# NB-Blue.net
KiCad netlist of a schematic drawn in Altium Designer
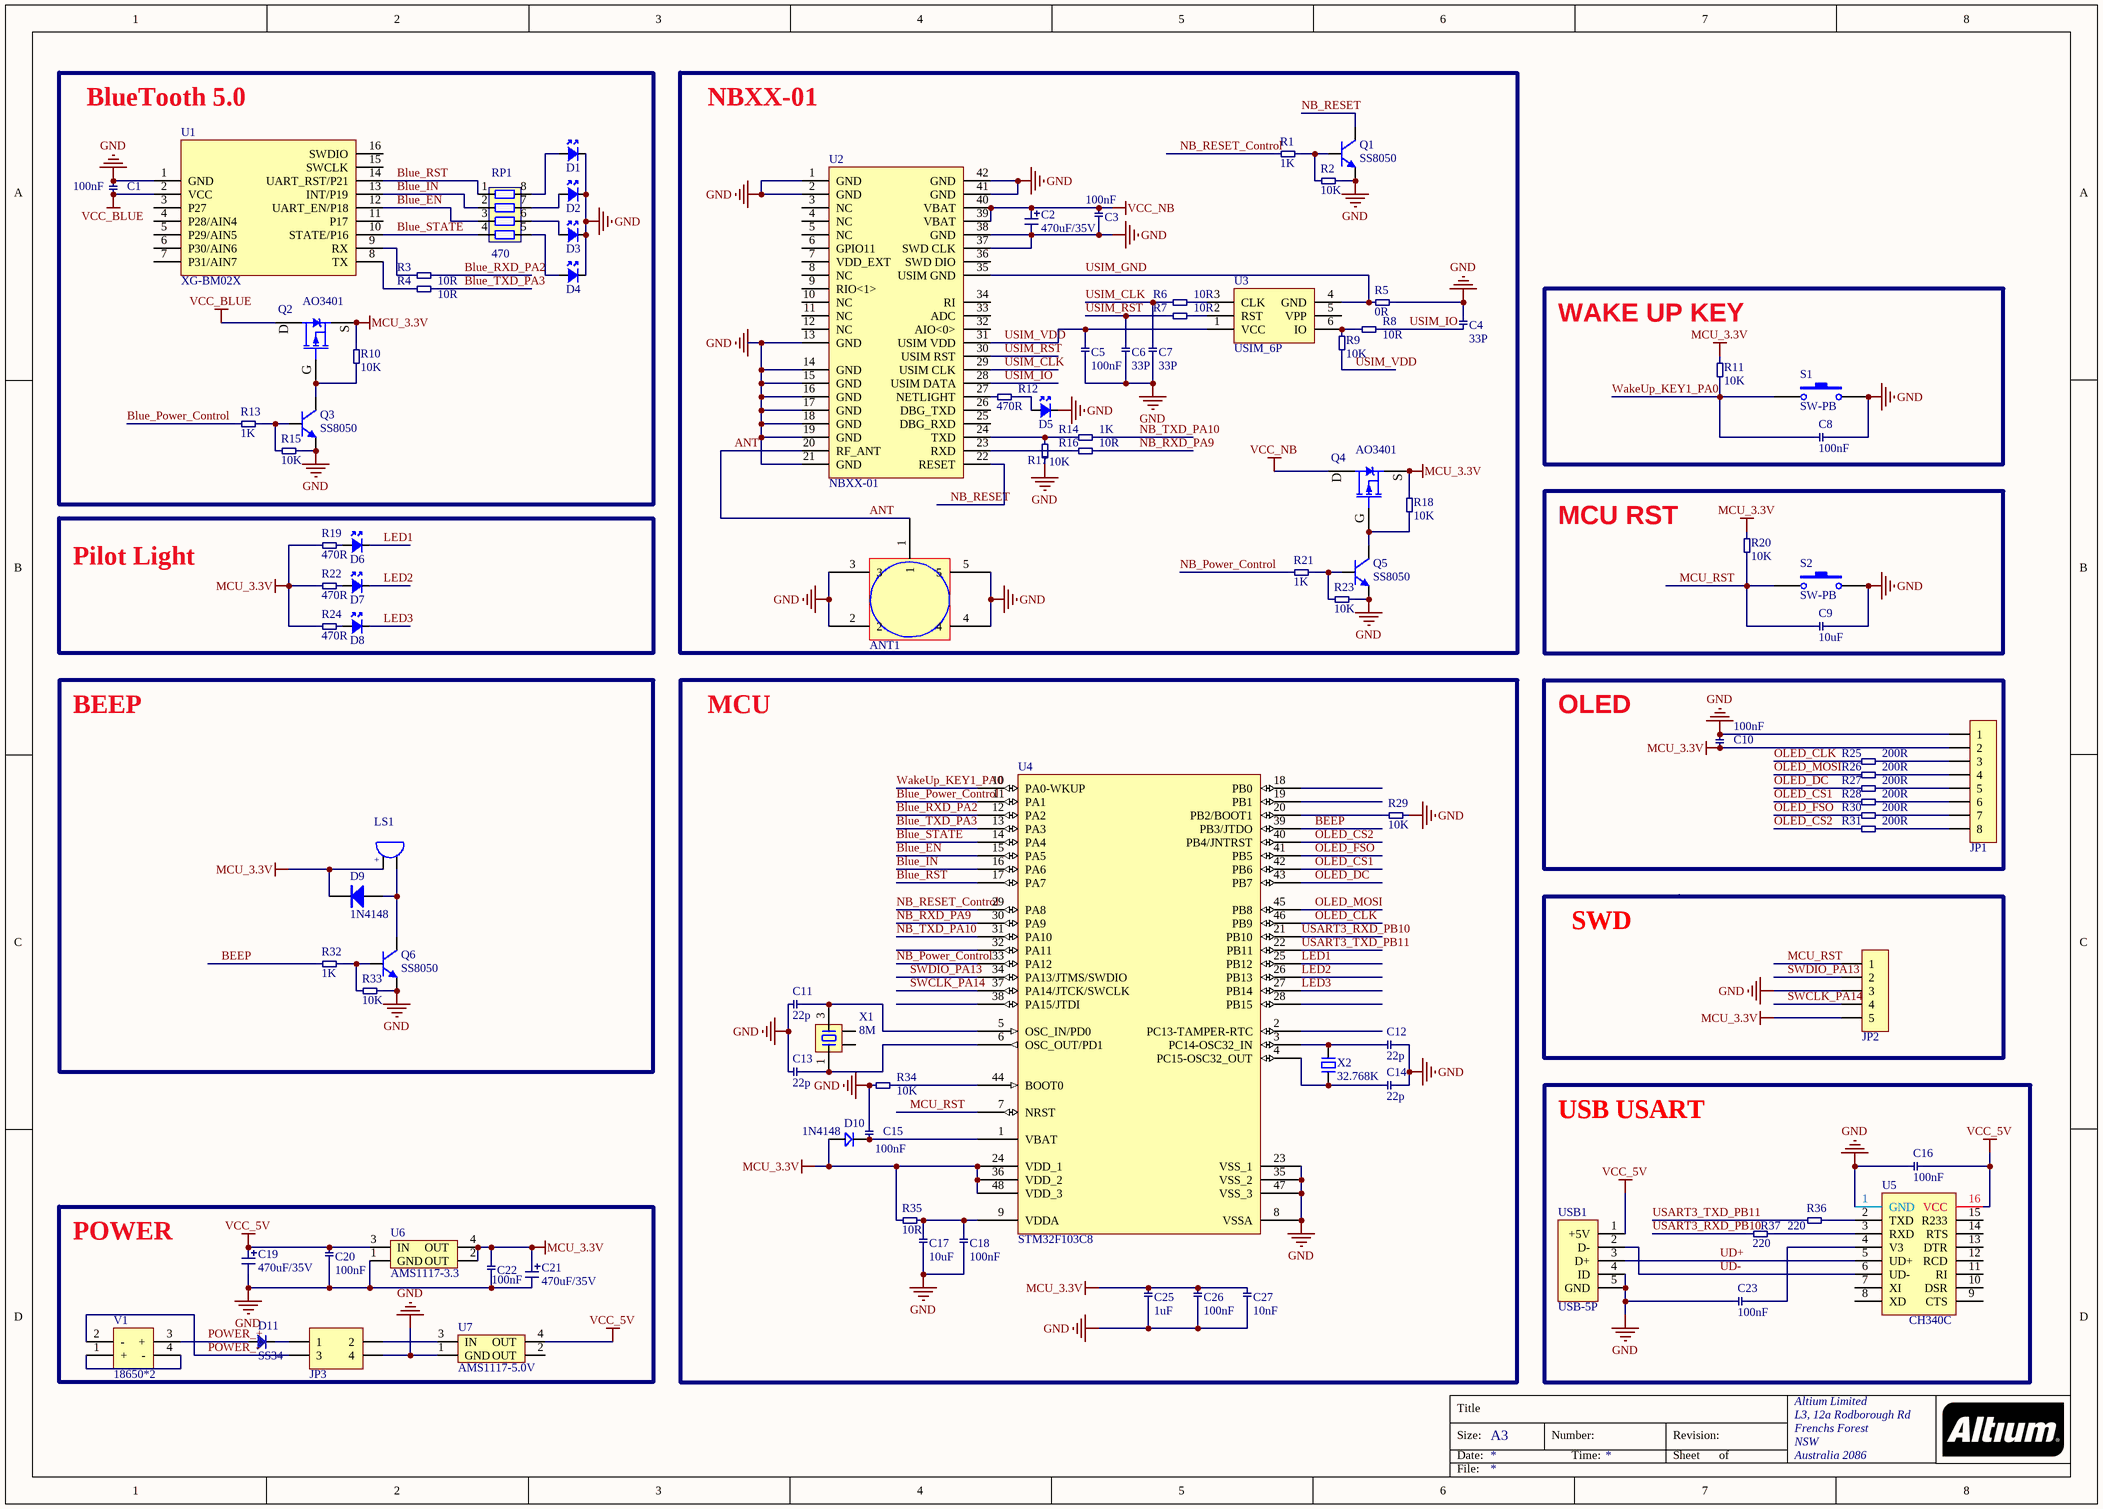
[diagram p0: NB-Blue.SchDoc]

(export (version "E")
  (design (tool "Eeschema 10.0.6"))
  (components
    (comp (ref "ANT1")
      (value "ANT")
      (footprint "SMA_FR")
      (description "SMA天线座")
      (libsource (lib "转接板顶板") (part "ANT"))
    )
    (comp (ref "C1") (value "100nF") (footprint "0603CC") (libsource (lib "LFZ@WLP") (part "cap")))
    (comp (ref "C2") (value "470uF/35V") (footprint "C3216") (libsource (lib "LFZ@WLP") (part "Ecap")))
    (comp (ref "C3") (value "100nF") (footprint "0603CC") (libsource (lib "LFZ@WLP") (part "cap")))
    (comp (ref "C4") (value "33P") (footprint "0603CC") (libsource (lib "LFZ@WLP") (part "cap")))
    (comp (ref "C5") (value "100nF") (footprint "0603CC") (libsource (lib "LFZ@WLP") (part "cap")))
    (comp (ref "C6") (value "33P") (footprint "0603CC") (libsource (lib "LFZ@WLP") (part "cap")))
    (comp (ref "C7") (value "33P") (footprint "0603CC") (libsource (lib "LFZ@WLP") (part "cap")))
    (comp (ref "C8") (value "100nF") (footprint "0603CC") (libsource (lib "LFZ@WLP") (part "cap")))
    (comp (ref "C9") (value "10uF") (footprint "0603CC") (libsource (lib "LFZ@WLP") (part "cap")))
    (comp (ref "C10") (value "100nF") (footprint "0603CC") (libsource (lib "LFZ@WLP") (part "cap")))
    (comp (ref "C11") (value "22p") (footprint "0603CC") (libsource (lib "LFZ@WLP") (part "cap")))
    (comp (ref "C12") (value "22p") (footprint "0603CC") (libsource (lib "LFZ@WLP") (part "cap")))
    (comp (ref "C13") (value "22p") (footprint "0603CC") (libsource (lib "LFZ@WLP") (part "cap")))
    (comp (ref "C14") (value "22p") (footprint "0603CC") (libsource (lib "LFZ@WLP") (part "cap")))
    (comp (ref "C15") (value "100nF") (footprint "0603CC") (libsource (lib "LFZ@WLP") (part "cap")))
    (comp (ref "C16") (value "100nF") (footprint "0603CC") (libsource (lib "LFZ@WLP") (part "cap")))
    (comp (ref "C17") (value "10uF") (footprint "0603CC") (libsource (lib "LFZ@WLP") (part "cap")))
    (comp (ref "C18") (value "100nF") (footprint "0603CC") (libsource (lib "LFZ@WLP") (part "cap")))
    (comp (ref "C19") (value "470uF/35V") (footprint "CD A(3216)") (libsource (lib "LFZ@WLP") (part "Ecap")))
    (comp (ref "C20") (value "100nF") (footprint "0603CC") (libsource (lib "LFZ@WLP") (part "cap")))
    (comp (ref "C21") (value "470uF/35V") (footprint "C3216") (libsource (lib "LFZ@WLP") (part "Ecap")))
    (comp (ref "C22") (value "100nF") (footprint "0603CC") (libsource (lib "LFZ@WLP") (part "cap")))
    (comp (ref "C23") (value "100nF") (footprint "0603CC") (libsource (lib "LFZ@WLP") (part "cap")))
    (comp (ref "C25") (value "1uF") (footprint "0603CC") (libsource (lib "LFZ@WLP") (part "cap")))
    (comp (ref "C26") (value "100nF") (footprint "0603CC") (libsource (lib "LFZ@WLP") (part "cap")))
    (comp (ref "C27") (value "10nF") (footprint "0603CC") (libsource (lib "LFZ@WLP") (part "cap")))
    (comp (ref "D1") (value "LED") (footprint "LED 0603G") (libsource (lib "LFZ@WLP") (part "LED")))
    (comp (ref "D2") (value "LED") (footprint "LED 0603G") (libsource (lib "LFZ@WLP") (part "LED")))
    (comp (ref "D3") (value "LED") (footprint "LED 0603G") (libsource (lib "LFZ@WLP") (part "LED")))
    (comp (ref "D4") (value "LED") (footprint "LED 0603G") (libsource (lib "LFZ@WLP") (part "LED")))
    (comp (ref "D5") (value "LED") (footprint "LED 0603G") (libsource (lib "LFZ@WLP") (part "LED")))
    (comp (ref "D6") (value "LED") (footprint "LED 3MM-G") (libsource (lib "LFZ@WLP") (part "LED")))
    (comp (ref "D7") (value "LED") (footprint "LED 3MM-G") (libsource (lib "LFZ@WLP") (part "LED")))
    (comp (ref "D8") (value "LED") (footprint "LED 3MM-G") (libsource (lib "LFZ@WLP") (part "LED")))
    (comp (ref "D9")
      (value "1N4148")
      (footprint "MINI_MELF (LL34)")
      (description "高速开关二极管")
      (fields (field (name "版权归属") "源创客"))
      (libsource (lib "8.1   - 二极管-整流桥") (part "1N4148"))
    )
    (comp (ref "D10")
      (value "1N4148")
      (footprint "MINI_MELF (LL34)")
      (libsource (lib "WarShip V3 STM32103封装库") (part "D"))
    )
    (comp (ref "D11") (value "SS34") (footprint "SMA") (libsource (lib "Diod") (part "Diod")))
    (comp (ref "JP1")
      (value "HDR-1X8")
      (footprint "HDR2.54-M-LI-8P")
      (description "8P接插件")
      (fields (field (name "版权归属") "源创客"))
      (libsource (lib "4.5   - 接插件-脚距2.54") (part "Header 8"))
    )
    (comp (ref "JP2")
      (value "HDR-1X5")
      (footprint "HDR2.54-LI-5P")
      (description "5P接插件")
      (fields (field (name "版权归属") "源创客"))
      (libsource (lib "4.5   - 接插件-脚距2.54") (part "Header 5"))
    )
    (comp (ref "JP3")
      (value "Header2X2")
      (footprint "HDR2.54-LI-2x2P")
      (description "2*2P接插件")
      (fields (field (name "版权归属") "源创客"))
      (libsource (lib "4.5   - 接插件-脚距2.54") (part "Header 2X2"))
    )
    (comp (ref "LS1")
      (value "DC5V")
      (footprint "BEEP 5x9x5.5")
      (description "蜂鸣器")
      (fields (field (name "版权归属") "源创客"))
      (libsource (lib "15.1 - 未分类器件") (part "BEEP"))
    )
    (comp (ref "Q1")
      (value "SS8050")
      (footprint "SOT23-3N")
      (description "高频放大-NPN型")
      (fields (field (name "版权归属") "源创客"))
      (libsource (lib "6.2   - 三极管") (part "8050-SMD"))
    )
    (comp (ref "Q2")
      (value "AO3401")
      (footprint "SOT23-3N")
      (description "P沟道场效应管")
      (fields (field (name "版权归属") "源创客"))
      (libsource (lib "6.1   - 场效应管-可控硅") (part "SI2301"))
    )
    (comp (ref "Q3")
      (value "SS8050")
      (footprint "SOT23-3N")
      (description "高频放大-NPN型")
      (fields (field (name "版权归属") "源创客"))
      (libsource (lib "6.2   - 三极管") (part "8050-SMD"))
    )
    (comp (ref "Q4")
      (value "AO3401")
      (footprint "SOT23-3N")
      (description "P沟道场效应管")
      (fields (field (name "版权归属") "源创客"))
      (libsource (lib "6.1   - 场效应管-可控硅") (part "SI2301"))
    )
    (comp (ref "Q5")
      (value "SS8050")
      (footprint "SOT23-3N")
      (description "高频放大-NPN型")
      (fields (field (name "版权归属") "源创客"))
      (libsource (lib "6.2   - 三极管") (part "8050-SMD"))
    )
    (comp (ref "Q6")
      (value "SS8050")
      (footprint "SOT23-3N")
      (description "高频放大-NPN型")
      (fields (field (name "版权归属") "源创客"))
      (libsource (lib "6.2   - 三极管") (part "8050-SMD"))
    )
    (comp (ref "R1") (value "1K") (footprint "0603RR") (libsource (lib "LFZ@WLP") (part "res")))
    (comp (ref "R2") (value "10K") (footprint "0603RR") (libsource (lib "LFZ@WLP") (part "res")))
    (comp (ref "R3") (value "10R") (footprint "0603RR") (libsource (lib "LFZ@WLP") (part "res")))
    (comp (ref "R4") (value "10R") (footprint "0603RR") (libsource (lib "LFZ@WLP") (part "res")))
    (comp (ref "R5") (value "0R") (footprint "0603RR") (libsource (lib "LFZ@WLP") (part "res")))
    (comp (ref "R6") (value "10R") (footprint "0603RR") (libsource (lib "LFZ@WLP") (part "res")))
    (comp (ref "R7") (value "10R") (footprint "0603RR") (libsource (lib "LFZ@WLP") (part "res")))
    (comp (ref "R8") (value "10R") (footprint "0603RR") (libsource (lib "LFZ@WLP") (part "res")))
    (comp (ref "R9") (value "10K") (footprint "0603RR") (libsource (lib "LFZ@WLP") (part "res")))
    (comp (ref "R10") (value "10K") (footprint "0603RR") (libsource (lib "LFZ@WLP") (part "res")))
    (comp (ref "R11") (value "10K") (footprint "0603RR") (libsource (lib "LFZ@WLP") (part "res")))
    (comp (ref "R12") (value "470R") (footprint "0603RR") (libsource (lib "LFZ@WLP") (part "res")))
    (comp (ref "R13") (value "1K") (footprint "0603RR") (libsource (lib "LFZ@WLP") (part "res")))
    (comp (ref "R14") (value "1K") (footprint "0603RR") (libsource (lib "LFZ@WLP") (part "res")))
    (comp (ref "R15") (value "10K") (footprint "0603RR") (libsource (lib "LFZ@WLP") (part "res")))
    (comp (ref "R16") (value "10R") (footprint "0603RR") (libsource (lib "LFZ@WLP") (part "res")))
    (comp (ref "R17") (value "10K") (footprint "0603RR") (libsource (lib "LFZ@WLP") (part "res")))
    (comp (ref "R18") (value "10K") (footprint "0603RR") (libsource (lib "LFZ@WLP") (part "res")))
    (comp (ref "R19") (value "470R") (footprint "0603RR") (libsource (lib "LFZ@WLP") (part "res")))
    (comp (ref "R20") (value "10K") (footprint "0603RR") (libsource (lib "LFZ@WLP") (part "res")))
    (comp (ref "R21") (value "1K") (footprint "0603RR") (libsource (lib "LFZ@WLP") (part "res")))
    (comp (ref "R22") (value "470R") (footprint "0603RR") (libsource (lib "LFZ@WLP") (part "res")))
    (comp (ref "R23") (value "10K") (footprint "0603RR") (libsource (lib "LFZ@WLP") (part "res")))
    (comp (ref "R24") (value "470R") (footprint "0603RR") (libsource (lib "LFZ@WLP") (part "res")))
    (comp (ref "R25") (value "200R") (footprint "0603RR") (libsource (lib "LFZ@WLP") (part "res")))
    (comp (ref "R26") (value "200R") (footprint "0603RR") (libsource (lib "LFZ@WLP") (part "res")))
    (comp (ref "R27") (value "200R") (footprint "0603RR") (libsource (lib "LFZ@WLP") (part "res")))
    (comp (ref "R28") (value "200R") (footprint "0603RR") (libsource (lib "LFZ@WLP") (part "res")))
    (comp (ref "R29") (value "10K") (footprint "0603RR") (libsource (lib "LFZ@WLP") (part "res")))
    (comp (ref "R30") (value "200R") (footprint "0603RR") (libsource (lib "LFZ@WLP") (part "res")))
    (comp (ref "R31") (value "200R") (footprint "0603RR") (libsource (lib "LFZ@WLP") (part "res")))
    (comp (ref "R32") (value "1K") (footprint "0603RR") (libsource (lib "LFZ@WLP") (part "res")))
    (comp (ref "R33") (value "10K") (footprint "0603RR") (libsource (lib "LFZ@WLP") (part "res")))
    (comp (ref "R34") (value "10K") (footprint "0603RR") (libsource (lib "LFZ@WLP") (part "res")))
    (comp (ref "R35") (value "10R") (footprint "0603RR") (libsource (lib "LFZ@WLP") (part "res")))
    (comp (ref "R36") (value "220") (footprint "0603RR") (libsource (lib "LFZ@WLP") (part "res")))
    (comp (ref "R37") (value "220") (footprint "0603RR") (libsource (lib "LFZ@WLP") (part "res")))
    (comp (ref "RP1") (value "470") (footprint "4x0603") (libsource (lib "LFZ@WLP") (part "Resistor_Pack")))
    (comp (ref "S1")
      (value "SW-PB")
      (footprint "TSW SMD-6*6*6")
      (description "Switch")
      (fields (field (name "PUBLISHER") "Altium Limited"))
      (libsource (lib "开关及电源") (part "SW-PB"))
    )
    (comp (ref "S2")
      (value "SW-PB")
      (footprint "TSW SMD-4*4*1.5")
      (description "Switch")
      (fields (field (name "PUBLISHER") "Altium Limited"))
      (libsource (lib "开关及电源") (part "SW-PB"))
    )
    (comp (ref "U1") (value "XG-BM02X") (footprint "XG-BM02X") (libsource (lib "XG-BM02") (part "XG-BM02X")))
    (comp (ref "U2")
      (value "NBXX-01")
      (footprint "X_LSD4NBN-LB05000001")
      (libsource (lib "XG-BM02") (part "NB"))
    )
    (comp (ref "U3") (value "USIM_6P") (footprint "SIM 6P 自弹") (libsource (lib "XG-BM02") (part "USIM-6P")))
    (comp (ref "U4")
      (value "STM32F103C8")
      (footprint "LQFP48 7X7_M")
      (description "Flaah:64/RAM:20/IO:36")
      (fields (field (name "版权归属") "源创客"))
      (libsource (lib "2.1   - STM32系列单片机") (part "STM32F103C8"))
    )
    (comp (ref "U5") (value "CH340C") (footprint "SOP16_L") (libsource (lib "LFZ@WLP") (part "CH340C")))
    (comp (ref "U6")
      (value "AMS1117-3.3")
      (footprint "SOT223_N")
      (libsource (lib "WarShip V3 STM32103封装库") (part "AMS1117"))
    )
    (comp (ref "U7")
      (value "AMS1117-5.0V")
      (footprint "SOT223_N")
      (libsource (lib "WarShip V3 STM32103封装库") (part "AMS1117"))
    )
    (comp (ref "USB1")
      (value "USB-5P")
      (footprint "USB-MICRO_A")
      (description "微型USB母座")
      (fields (field (name "版权归属") "源创客"))
      (libsource (lib "4.1   - 接口类") (part "USB-5P"))
    )
    (comp (ref "V1") (value "18650*2") (footprint "18650*2") (libsource (lib "XG-BM02") (part "18650-2P")))
    (comp (ref "X1")
      (value "8M")
      (footprint "OSC 3225-4P")
      (description "4脚无源晶振")
      (fields (field (name "版权归属") "源创客"))
      (libsource (lib "10.1 - 保险丝-晶振") (part "XTAL-4P"))
    )
    (comp (ref "X2")
      (value "32.768K")
      (footprint "OSC 3215-2P")
      (description "2脚无源脚晶振")
      (fields (field (name "版权归属") "源创客"))
      (libsource (lib "10.1 - 保险丝-晶振") (part "XTAL-2P"))
    )
  )
  (nets
    (net (code "1") (name "/ANT") (class "Default")
      (node (ref "ANT1") (pin "1") (pinfunction "1_1") (pintype "passive"))
      (node (ref "U2") (pin "20") (pinfunction "RF_ANT_20") (pintype "passive"))
    )
    (net (code "2") (name "/BEEP") (class "Default")
      (node (ref "R32") (pin "1") (pinfunction "1_1") (pintype "passive"))
      (node (ref "U4") (pin "39") (pinfunction "PB3/JTDO_39") (pintype "bidirectional"))
    )
    (net (code "3") (name "/Blue_EN") (class "Default")
      (node (ref "RP1") (pin "3") (pinfunction "3_3") (pintype "passive"))
      (node (ref "U1") (pin "12") (pinfunction "UART_EN/P18_12") (pintype "passive"))
      (node (ref "U4") (pin "15") (pinfunction "PA5_15") (pintype "bidirectional"))
    )
    (net (code "4") (name "/Blue_IN") (class "Default")
      (node (ref "RP1") (pin "2") (pinfunction "2_2") (pintype "passive"))
      (node (ref "U1") (pin "13") (pinfunction "INT/P19_13") (pintype "passive"))
      (node (ref "U4") (pin "16") (pinfunction "PA6_16") (pintype "bidirectional"))
    )
    (net (code "5") (name "/Blue_Power_Control") (class "Default")
      (node (ref "R13") (pin "1") (pinfunction "1_1") (pintype "passive"))
      (node (ref "U4") (pin "11") (pinfunction "PA1_11") (pintype "bidirectional"))
    )
    (net (code "6") (name "/Blue_RST") (class "Default")
      (node (ref "RP1") (pin "1") (pinfunction "1_1") (pintype "passive"))
      (node (ref "U1") (pin "14") (pinfunction "UART_RST/P21_14") (pintype "passive"))
      (node (ref "U4") (pin "17") (pinfunction "PA7_17") (pintype "bidirectional"))
    )
    (net (code "7") (name "/Blue_RXD_PA2") (class "Default")
      (node (ref "R3") (pin "2") (pinfunction "2_2") (pintype "passive"))
      (node (ref "U4") (pin "12") (pinfunction "PA2_12") (pintype "bidirectional"))
    )
    (net (code "8") (name "/Blue_STATE") (class "Default")
      (node (ref "RP1") (pin "4") (pinfunction "4_4") (pintype "passive"))
      (node (ref "U1") (pin "10") (pinfunction "STATE/P16_10") (pintype "passive"))
      (node (ref "U4") (pin "14") (pinfunction "PA4_14") (pintype "bidirectional"))
    )
    (net (code "9") (name "/Blue_TXD_PA3") (class "Default")
      (node (ref "R4") (pin "2") (pinfunction "2_2") (pintype "passive"))
      (node (ref "U4") (pin "13") (pinfunction "PA3_13") (pintype "bidirectional"))
    )
    (net (code "10") (name "/LED1") (class "Default")
      (node (ref "D6") (pin "2") (pinfunction "CATHODE_2") (pintype "passive"))
      (node (ref "U4") (pin "25") (pinfunction "PB12_25") (pintype "bidirectional"))
    )
    (net (code "11") (name "/LED2") (class "Default")
      (node (ref "D7") (pin "2") (pinfunction "CATHODE_2") (pintype "passive"))
      (node (ref "U4") (pin "26") (pinfunction "PB13_26") (pintype "bidirectional"))
    )
    (net (code "12") (name "/LED3") (class "Default")
      (node (ref "D8") (pin "2") (pinfunction "CATHODE_2") (pintype "passive"))
      (node (ref "U4") (pin "27") (pinfunction "PB14_27") (pintype "bidirectional"))
    )
    (net (code "13") (name "/MCU_RST") (class "Default")
      (node (ref "C9") (pin "2") (pinfunction "2_2") (pintype "passive"))
      (node (ref "JP2") (pin "1") (pinfunction "1_1") (pintype "passive"))
      (node (ref "R20") (pin "1") (pinfunction "1_1") (pintype "passive"))
      (node (ref "S2") (pin "1") (pinfunction "1_1") (pintype "passive"))
      (node (ref "U4") (pin "7") (pinfunction "NRST_7") (pintype "bidirectional"))
    )
    (net (code "14") (name "/NB_Power_Control") (class "Default")
      (node (ref "R21") (pin "1") (pinfunction "1_1") (pintype "passive"))
      (node (ref "U4") (pin "33") (pinfunction "PA12_33") (pintype "bidirectional"))
    )
    (net (code "15") (name "/NB_RESET") (class "Default")
      (node (ref "Q1") (pin "3") (pinfunction "C_3") (pintype "passive"))
      (node (ref "U2") (pin "22") (pinfunction "RESET_22") (pintype "passive"))
    )
    (net (code "16") (name "/NB_RESET_Control") (class "Default")
      (node (ref "R1") (pin "1") (pinfunction "1_1") (pintype "passive"))
      (node (ref "U4") (pin "29") (pinfunction "PA8_29") (pintype "bidirectional"))
    )
    (net (code "17") (name "/NB_RXD_PA9") (class "Default")
      (node (ref "R16") (pin "2") (pinfunction "2_2") (pintype "passive"))
      (node (ref "U4") (pin "30") (pinfunction "PA9_30") (pintype "bidirectional"))
    )
    (net (code "18") (name "/NB_TXD_PA10") (class "Default")
      (node (ref "R14") (pin "2") (pinfunction "2_2") (pintype "passive"))
      (node (ref "U4") (pin "31") (pinfunction "PA10_31") (pintype "bidirectional"))
    )
    (net (code "19") (name "/OLED_CLK") (class "Default")
      (node (ref "R25") (pin "1") (pinfunction "1_1") (pintype "passive"))
      (node (ref "U4") (pin "46") (pinfunction "PB9_46") (pintype "bidirectional"))
    )
    (net (code "20") (name "/OLED_CS1") (class "Default")
      (node (ref "R28") (pin "1") (pinfunction "1_1") (pintype "passive"))
      (node (ref "U4") (pin "42") (pinfunction "PB6_42") (pintype "bidirectional"))
    )
    (net (code "21") (name "/OLED_CS2") (class "Default")
      (node (ref "R31") (pin "1") (pinfunction "1_1") (pintype "passive"))
      (node (ref "U4") (pin "40") (pinfunction "PB4/JNTRST_40") (pintype "bidirectional"))
    )
    (net (code "22") (name "/OLED_DC") (class "Default")
      (node (ref "R27") (pin "1") (pinfunction "1_1") (pintype "passive"))
      (node (ref "U4") (pin "43") (pinfunction "PB7_43") (pintype "bidirectional"))
    )
    (net (code "23") (name "/OLED_FSO") (class "Default")
      (node (ref "R30") (pin "1") (pinfunction "1_1") (pintype "passive"))
      (node (ref "U4") (pin "41") (pinfunction "PB5_41") (pintype "bidirectional"))
    )
    (net (code "24") (name "/OLED_MOSI") (class "Default")
      (node (ref "R26") (pin "1") (pinfunction "1_1") (pintype "passive"))
      (node (ref "U4") (pin "45") (pinfunction "PB8_45") (pintype "bidirectional"))
    )
    (net (code "25") (name "/POWER_+") (class "Default")
      (node (ref "D11") (pin "1") (pinfunction "ANODE_1") (pintype "passive"))
      (node (ref "V1") (pin "3") (pinfunction "+_3") (pintype "passive"))
    )
    (net (code "26") (name "/POWER_-") (class "Default")
      (node (ref "JP3") (pin "3") (pinfunction "3_3") (pintype "passive"))
      (node (ref "V1") (pin "2") (pinfunction "-_2") (pintype "passive"))
    )
    (net (code "27") (name "/SWCLK_PA14") (class "Default")
      (node (ref "JP2") (pin "4") (pinfunction "4_4") (pintype "passive"))
      (node (ref "U4") (pin "37") (pinfunction "PA14/JTCK/SWCLK_37") (pintype "bidirectional"))
    )
    (net (code "28") (name "/SWDIO_PA13") (class "Default")
      (node (ref "JP2") (pin "2") (pinfunction "2_2") (pintype "passive"))
      (node (ref "U4") (pin "34") (pinfunction "PA13/JTMS/SWDIO_34") (pintype "bidirectional"))
    )
    (net (code "29") (name "/UD+") (class "Default")
      (node (ref "U5") (pin "5") (pinfunction "UD+_5") (pintype "passive"))
      (node (ref "USB1") (pin "3") (pinfunction "D+_3") (pintype "passive"))
    )
    (net (code "30") (name "/UD-") (class "Default")
      (node (ref "U5") (pin "6") (pinfunction "UD-_6") (pintype "passive"))
      (node (ref "USB1") (pin "2") (pinfunction "D-_2") (pintype "passive"))
    )
    (net (code "31") (name "/USART3_RXD_PB10") (class "Default")
      (node (ref "R37") (pin "1") (pinfunction "1_1") (pintype "passive"))
      (node (ref "U4") (pin "21") (pinfunction "PB10_21") (pintype "bidirectional"))
    )
    (net (code "32") (name "/USART3_TXD_PB11") (class "Default")
      (node (ref "R36") (pin "1") (pinfunction "1_1") (pintype "passive"))
      (node (ref "U4") (pin "22") (pinfunction "PB11_22") (pintype "bidirectional"))
    )
    (net (code "33") (name "/USIM_CLK") (class "Default")
      (node (ref "C7") (pin "2") (pinfunction "2_2") (pintype "passive"))
      (node (ref "R6") (pin "1") (pinfunction "1_1") (pintype "passive"))
      (node (ref "U2") (pin "29") (pinfunction "USIM_CLK_29") (pintype "passive"))
    )
    (net (code "34") (name "/USIM_GND") (class "Default")
      (node (ref "R5") (pin "1") (pinfunction "1_1") (pintype "passive"))
      (node (ref "U2") (pin "35") (pinfunction "USIM_GND_35") (pintype "passive"))
      (node (ref "U3") (pin "4") (pinfunction "GND_4") (pintype "passive"))
    )
    (net (code "35") (name "/USIM_IO") (class "Default")
      (node (ref "C4") (pin "1") (pinfunction "1_1") (pintype "passive"))
      (node (ref "R8") (pin "1") (pinfunction "1_1") (pintype "passive"))
      (node (ref "U2") (pin "28") (pinfunction "USIM_DATA_28") (pintype "passive"))
    )
    (net (code "36") (name "/USIM_RST") (class "Default")
      (node (ref "C6") (pin "2") (pinfunction "2_2") (pintype "passive"))
      (node (ref "R7") (pin "1") (pinfunction "1_1") (pintype "passive"))
      (node (ref "U2") (pin "30") (pinfunction "USIM_RST_30") (pintype "passive"))
    )
    (net (code "37") (name "/USIM_VDD") (class "Default")
      (node (ref "C5") (pin "2") (pinfunction "2_2") (pintype "passive"))
      (node (ref "R9") (pin "1") (pinfunction "1_1") (pintype "passive"))
      (node (ref "U2") (pin "31") (pinfunction "USIM_VDD_31") (pintype "passive"))
      (node (ref "U3") (pin "1") (pinfunction "VCC_1") (pintype "passive"))
    )
    (net (code "38") (name "/WakeUp_KEY1_PA0") (class "Default")
      (node (ref "C8") (pin "1") (pinfunction "1_1") (pintype "passive"))
      (node (ref "R11") (pin "1") (pinfunction "1_1") (pintype "passive"))
      (node (ref "S1") (pin "1") (pinfunction "1_1") (pintype "passive"))
      (node (ref "U4") (pin "10") (pinfunction "PA0-WKUP_10") (pintype "bidirectional"))
    )
    (net (code "39") (name "GND") (class "Default")
      (node (ref "ANT1") (pin "2") (pinfunction "2_2") (pintype "passive"))
      (node (ref "ANT1") (pin "3") (pinfunction "3_3") (pintype "passive"))
      (node (ref "ANT1") (pin "4") (pinfunction "4_4") (pintype "passive"))
      (node (ref "ANT1") (pin "5") (pinfunction "5_5") (pintype "passive"))
      (node (ref "C1") (pin "2") (pinfunction "2_2") (pintype "passive"))
      (node (ref "C10") (pin "2") (pinfunction "2_2") (pintype "passive"))
      (node (ref "C11") (pin "1") (pinfunction "1_1") (pintype "passive"))
      (node (ref "C12") (pin "2") (pinfunction "2_2") (pintype "passive"))
      (node (ref "C13") (pin "1") (pinfunction "1_1") (pintype "passive"))
      (node (ref "C14") (pin "2") (pinfunction "2_2") (pintype "passive"))
      (node (ref "C15") (pin "2") (pinfunction "2_2") (pintype "passive"))
      (node (ref "C16") (pin "2") (pinfunction "2_2") (pintype "passive"))
      (node (ref "C17") (pin "1") (pinfunction "1_1") (pintype "passive"))
      (node (ref "C18") (pin "1") (pinfunction "1_1") (pintype "passive"))
      (node (ref "C19") (pin "2") (pinfunction "2_2") (pintype "passive"))
      (node (ref "C2") (pin "2") (pinfunction "2_2") (pintype "passive"))
      (node (ref "C20") (pin "1") (pinfunction "1_1") (pintype "passive"))
      (node (ref "C21") (pin "2") (pinfunction "2_2") (pintype "passive"))
      (node (ref "C22") (pin "1") (pinfunction "1_1") (pintype "passive"))
      (node (ref "C23") (pin "2") (pinfunction "2_2") (pintype "passive"))
      (node (ref "C25") (pin "1") (pinfunction "1_1") (pintype "passive"))
      (node (ref "C26") (pin "1") (pinfunction "1_1") (pintype "passive"))
      (node (ref "C27") (pin "1") (pinfunction "1_1") (pintype "passive"))
      (node (ref "C3") (pin "1") (pinfunction "1_1") (pintype "passive"))
      (node (ref "C4") (pin "2") (pinfunction "2_2") (pintype "passive"))
      (node (ref "C5") (pin "1") (pinfunction "1_1") (pintype "passive"))
      (node (ref "C6") (pin "1") (pinfunction "1_1") (pintype "passive"))
      (node (ref "C7") (pin "1") (pinfunction "1_1") (pintype "passive"))
      (node (ref "C8") (pin "2") (pinfunction "2_2") (pintype "passive"))
      (node (ref "C9") (pin "1") (pinfunction "1_1") (pintype "passive"))
      (node (ref "D1") (pin "2") (pinfunction "CATHODE_2") (pintype "passive"))
      (node (ref "D2") (pin "2") (pinfunction "CATHODE_2") (pintype "passive"))
      (node (ref "D3") (pin "2") (pinfunction "CATHODE_2") (pintype "passive"))
      (node (ref "D4") (pin "2") (pinfunction "CATHODE_2") (pintype "passive"))
      (node (ref "D5") (pin "2") (pinfunction "CATHODE_2") (pintype "passive"))
      (node (ref "JP1") (pin "1") (pinfunction "1_1") (pintype "passive"))
      (node (ref "JP2") (pin "3") (pinfunction "3_3") (pintype "passive"))
      (node (ref "JP3") (pin "4") (pinfunction "4_4") (pintype "passive"))
      (node (ref "Q1") (pin "2") (pinfunction "E_2") (pintype "passive"))
      (node (ref "Q3") (pin "2") (pinfunction "E_2") (pintype "passive"))
      (node (ref "Q5") (pin "2") (pinfunction "E_2") (pintype "passive"))
      (node (ref "Q6") (pin "2") (pinfunction "E_2") (pintype "passive"))
      (node (ref "R15") (pin "2") (pinfunction "2_2") (pintype "passive"))
      (node (ref "R17") (pin "2") (pinfunction "2_2") (pintype "passive"))
      (node (ref "R2") (pin "2") (pinfunction "2_2") (pintype "passive"))
      (node (ref "R23") (pin "2") (pinfunction "2_2") (pintype "passive"))
      (node (ref "R29") (pin "2") (pinfunction "2_2") (pintype "passive"))
      (node (ref "R33") (pin "2") (pinfunction "2_2") (pintype "passive"))
      (node (ref "R34") (pin "1") (pinfunction "1_1") (pintype "passive"))
      (node (ref "R5") (pin "2") (pinfunction "2_2") (pintype "passive"))
      (node (ref "S1") (pin "2") (pinfunction "2_2") (pintype "passive"))
      (node (ref "S2") (pin "2") (pinfunction "2_2") (pintype "passive"))
      (node (ref "U1") (pin "1") (pinfunction "GND_1") (pintype "passive"))
      (node (ref "U2") (pin "1") (pinfunction "GND_1") (pintype "passive"))
      (node (ref "U2") (pin "13") (pinfunction "GND_13") (pintype "passive"))
      (node (ref "U2") (pin "14") (pinfunction "GND_14") (pintype "passive"))
      (node (ref "U2") (pin "15") (pinfunction "GND_15") (pintype "passive"))
      (node (ref "U2") (pin "16") (pinfunction "GND_16") (pintype "passive"))
      (node (ref "U2") (pin "17") (pinfunction "GND_17") (pintype "passive"))
      (node (ref "U2") (pin "18") (pinfunction "GND_18") (pintype "passive"))
      (node (ref "U2") (pin "19") (pinfunction "GND_19") (pintype "passive"))
      (node (ref "U2") (pin "2") (pinfunction "GND_2") (pintype "passive"))
      (node (ref "U2") (pin "21") (pinfunction "GND_21") (pintype "passive"))
      (node (ref "U2") (pin "37") (pinfunction "SWD_CLK_37") (pintype "passive"))
      (node (ref "U2") (pin "38") (pinfunction "GND_38") (pintype "passive"))
      (node (ref "U2") (pin "41") (pinfunction "GND_41") (pintype "passive"))
      (node (ref "U2") (pin "42") (pinfunction "GND_42") (pintype "passive"))
      (node (ref "U4") (pin "23") (pinfunction "VSS_1_23") (pintype "power_in"))
      (node (ref "U4") (pin "35") (pinfunction "VSS_2_35") (pintype "power_in"))
      (node (ref "U4") (pin "47") (pinfunction "VSS_3_47") (pintype "power_in"))
      (node (ref "U4") (pin "8") (pinfunction "VSSA_8") (pintype "power_in"))
      (node (ref "U5") (pin "1") (pinfunction "GND_1") (pintype "passive"))
      (node (ref "U6") (pin "1") (pinfunction "GND_1") (pintype "passive"))
      (node (ref "U7") (pin "1") (pinfunction "GND_1") (pintype "passive"))
      (node (ref "USB1") (pin "4") (pinfunction "ID_4") (pintype "passive"))
      (node (ref "USB1") (pin "5") (pinfunction "GND_5") (pintype "passive"))
    )
    (net (code "40") (name "MCU_3.3V") (class "Default")
      (node (ref "C10") (pin "1") (pinfunction "1_1") (pintype "passive"))
      (node (ref "C21") (pin "1") (pinfunction "1_1") (pintype "passive"))
      (node (ref "C22") (pin "2") (pinfunction "2_2") (pintype "passive"))
      (node (ref "C25") (pin "2") (pinfunction "2_2") (pintype "passive"))
      (node (ref "C26") (pin "2") (pinfunction "2_2") (pintype "passive"))
      (node (ref "C27") (pin "2") (pinfunction "2_2") (pintype "passive"))
      (node (ref "D10") (pin "1") (pintype "passive"))
      (node (ref "D9") (pin "2") (pinfunction "K_2") (pintype "passive"))
      (node (ref "JP1") (pin "2") (pinfunction "2_2") (pintype "passive"))
      (node (ref "JP2") (pin "5") (pinfunction "5_5") (pintype "passive"))
      (node (ref "LS1") (pin "1") (pinfunction "1_1") (pintype "passive"))
      (node (ref "Q2") (pin "2") (pinfunction "S_2") (pintype "passive"))
      (node (ref "Q4") (pin "2") (pinfunction "S_2") (pintype "passive"))
      (node (ref "R10") (pin "2") (pinfunction "2_2") (pintype "passive"))
      (node (ref "R11") (pin "2") (pinfunction "2_2") (pintype "passive"))
      (node (ref "R18") (pin "2") (pinfunction "2_2") (pintype "passive"))
      (node (ref "R19") (pin "1") (pinfunction "1_1") (pintype "passive"))
      (node (ref "R20") (pin "2") (pinfunction "2_2") (pintype "passive"))
      (node (ref "R22") (pin "1") (pinfunction "1_1") (pintype "passive"))
      (node (ref "R24") (pin "1") (pinfunction "1_1") (pintype "passive"))
      (node (ref "R35") (pin "1") (pinfunction "1_1") (pintype "passive"))
      (node (ref "U4") (pin "24") (pinfunction "VDD_1_24") (pintype "power_in"))
      (node (ref "U4") (pin "36") (pinfunction "VDD_2_36") (pintype "power_in"))
      (node (ref "U4") (pin "48") (pinfunction "VDD_3_48") (pintype "power_in"))
      (node (ref "U6") (pin "2") (pinfunction "OUT_2") (pintype "passive"))
      (node (ref "U6") (pin "4") (pinfunction "OUT_4") (pintype "passive"))
    )
    (net (code "41") (name "Net-(D1-ANODE)") (class "Default")
      (node (ref "D1") (pin "1") (pinfunction "ANODE_1") (pintype "passive"))
      (node (ref "RP1") (pin "8") (pinfunction "8_8") (pintype "passive"))
    )
    (net (code "42") (name "Net-(D2-ANODE)") (class "Default")
      (node (ref "D2") (pin "1") (pinfunction "ANODE_1") (pintype "passive"))
      (node (ref "RP1") (pin "7") (pinfunction "7_7") (pintype "passive"))
    )
    (net (code "43") (name "Net-(D3-ANODE)") (class "Default")
      (node (ref "D3") (pin "1") (pinfunction "ANODE_1") (pintype "passive"))
      (node (ref "RP1") (pin "6") (pinfunction "6_6") (pintype "passive"))
    )
    (net (code "44") (name "Net-(D4-ANODE)") (class "Default")
      (node (ref "D4") (pin "1") (pinfunction "ANODE_1") (pintype "passive"))
      (node (ref "RP1") (pin "5") (pinfunction "5_5") (pintype "passive"))
    )
    (net (code "45") (name "Net-(D5-ANODE)") (class "Default")
      (node (ref "D5") (pin "1") (pinfunction "ANODE_1") (pintype "passive"))
      (node (ref "R12") (pin "2") (pinfunction "2_2") (pintype "passive"))
    )
    (net (code "46") (name "Net-(D6-ANODE)") (class "Default")
      (node (ref "D6") (pin "1") (pinfunction "ANODE_1") (pintype "passive"))
      (node (ref "R19") (pin "2") (pinfunction "2_2") (pintype "passive"))
    )
    (net (code "47") (name "Net-(D7-ANODE)") (class "Default")
      (node (ref "D7") (pin "1") (pinfunction "ANODE_1") (pintype "passive"))
      (node (ref "R22") (pin "2") (pinfunction "2_2") (pintype "passive"))
    )
    (net (code "48") (name "Net-(D8-ANODE)") (class "Default")
      (node (ref "D8") (pin "1") (pinfunction "ANODE_1") (pintype "passive"))
      (node (ref "R24") (pin "2") (pinfunction "2_2") (pintype "passive"))
    )
    (net (code "49") (name "Net-(D9-A)") (class "Default")
      (node (ref "D9") (pin "1") (pinfunction "A_1") (pintype "passive"))
      (node (ref "LS1") (pin "2") (pinfunction "2_2") (pintype "passive"))
      (node (ref "Q6") (pin "3") (pinfunction "C_3") (pintype "passive"))
    )
    (net (code "50") (name "Net-(D11-CATHODE)") (class "Default")
      (node (ref "D11") (pin "2") (pinfunction "CATHODE_2") (pintype "passive"))
      (node (ref "JP3") (pin "1") (pinfunction "1_1") (pintype "passive"))
    )
    (net (code "51") (name "Net-(JP1-Pad3)") (class "Default")
      (node (ref "JP1") (pin "3") (pinfunction "3_3") (pintype "passive"))
      (node (ref "R25") (pin "2") (pinfunction "2_2") (pintype "passive"))
    )
    (net (code "52") (name "Net-(JP1-Pad4)") (class "Default")
      (node (ref "JP1") (pin "4") (pinfunction "4_4") (pintype "passive"))
      (node (ref "R26") (pin "2") (pinfunction "2_2") (pintype "passive"))
    )
    (net (code "53") (name "Net-(JP1-Pad5)") (class "Default")
      (node (ref "JP1") (pin "5") (pinfunction "5_5") (pintype "passive"))
      (node (ref "R27") (pin "2") (pinfunction "2_2") (pintype "passive"))
    )
    (net (code "54") (name "Net-(JP1-Pad6)") (class "Default")
      (node (ref "JP1") (pin "6") (pinfunction "6_6") (pintype "passive"))
      (node (ref "R28") (pin "2") (pinfunction "2_2") (pintype "passive"))
    )
    (net (code "55") (name "Net-(JP1-Pad7)") (class "Default")
      (node (ref "JP1") (pin "7") (pinfunction "7_7") (pintype "passive"))
      (node (ref "R30") (pin "2") (pinfunction "2_2") (pintype "passive"))
    )
    (net (code "56") (name "Net-(JP1-Pad8)") (class "Default")
      (node (ref "JP1") (pin "8") (pinfunction "8_8") (pintype "passive"))
      (node (ref "R31") (pin "2") (pinfunction "2_2") (pintype "passive"))
    )
    (net (code "57") (name "Net-(Q1-B)") (class "Default")
      (node (ref "Q1") (pin "1") (pinfunction "B_1") (pintype "passive"))
      (node (ref "R1") (pin "2") (pinfunction "2_2") (pintype "passive"))
      (node (ref "R2") (pin "1") (pinfunction "1_1") (pintype "passive"))
    )
    (net (code "58") (name "Net-(Q2-G)") (class "Default")
      (node (ref "Q2") (pin "1") (pinfunction "G_1") (pintype "passive"))
      (node (ref "Q3") (pin "3") (pinfunction "C_3") (pintype "passive"))
      (node (ref "R10") (pin "1") (pinfunction "1_1") (pintype "passive"))
    )
    (net (code "59") (name "Net-(Q3-B)") (class "Default")
      (node (ref "Q3") (pin "1") (pinfunction "B_1") (pintype "passive"))
      (node (ref "R13") (pin "2") (pinfunction "2_2") (pintype "passive"))
      (node (ref "R15") (pin "1") (pinfunction "1_1") (pintype "passive"))
    )
    (net (code "60") (name "Net-(Q4-G)") (class "Default")
      (node (ref "Q4") (pin "1") (pinfunction "G_1") (pintype "passive"))
      (node (ref "Q5") (pin "3") (pinfunction "C_3") (pintype "passive"))
      (node (ref "R18") (pin "1") (pinfunction "1_1") (pintype "passive"))
    )
    (net (code "61") (name "Net-(Q5-B)") (class "Default")
      (node (ref "Q5") (pin "1") (pinfunction "B_1") (pintype "passive"))
      (node (ref "R21") (pin "2") (pinfunction "2_2") (pintype "passive"))
      (node (ref "R23") (pin "1") (pinfunction "1_1") (pintype "passive"))
    )
    (net (code "62") (name "Net-(Q6-B)") (class "Default")
      (node (ref "Q6") (pin "1") (pinfunction "B_1") (pintype "passive"))
      (node (ref "R32") (pin "2") (pinfunction "2_2") (pintype "passive"))
      (node (ref "R33") (pin "1") (pinfunction "1_1") (pintype "passive"))
    )
    (net (code "63") (name "Net-(U1-RX)") (class "Default")
      (node (ref "R3") (pin "1") (pinfunction "1_1") (pintype "passive"))
      (node (ref "U1") (pin "9") (pinfunction "RX_9") (pintype "passive"))
    )
    (net (code "64") (name "Net-(U1-TX)") (class "Default")
      (node (ref "R4") (pin "1") (pinfunction "1_1") (pintype "passive"))
      (node (ref "U1") (pin "8") (pinfunction "TX_8") (pintype "passive"))
    )
    (net (code "65") (name "Net-(U2-NETLIGHT)") (class "Default")
      (node (ref "R12") (pin "1") (pinfunction "1_1") (pintype "passive"))
      (node (ref "U2") (pin "27") (pinfunction "NETLIGHT_27") (pintype "passive"))
    )
    (net (code "66") (name "Net-(U2-RXD)") (class "Default")
      (node (ref "R16") (pin "1") (pinfunction "1_1") (pintype "passive"))
      (node (ref "U2") (pin "23") (pinfunction "RXD_23") (pintype "passive"))
    )
    (net (code "67") (name "Net-(U2-TXD)") (class "Default")
      (node (ref "R14") (pin "1") (pinfunction "1_1") (pintype "passive"))
      (node (ref "R17") (pin "1") (pinfunction "1_1") (pintype "passive"))
      (node (ref "U2") (pin "24") (pinfunction "TXD_24") (pintype "passive"))
    )
    (net (code "68") (name "Net-(U3-CLK)") (class "Default")
      (node (ref "R6") (pin "2") (pinfunction "2_2") (pintype "passive"))
      (node (ref "U3") (pin "3") (pinfunction "CLK_3") (pintype "passive"))
    )
    (net (code "69") (name "Net-(U3-IO)") (class "Default")
      (node (ref "R8") (pin "2") (pinfunction "2_2") (pintype "passive"))
      (node (ref "R9") (pin "2") (pinfunction "2_2") (pintype "passive"))
      (node (ref "U3") (pin "6") (pinfunction "IO_6") (pintype "passive"))
    )
    (net (code "70") (name "Net-(U3-RST)") (class "Default")
      (node (ref "R7") (pin "2") (pinfunction "2_2") (pintype "passive"))
      (node (ref "U3") (pin "2") (pinfunction "RST_2") (pintype "passive"))
    )
    (net (code "71") (name "Net-(U4-BOOT0)") (class "Default")
      (node (ref "R34") (pin "2") (pinfunction "2_2") (pintype "passive"))
      (node (ref "U4") (pin "44") (pinfunction "BOOT0_44") (pintype "input"))
    )
    (net (code "72") (name "Net-(U4-OSC_IN{slash}PD0)") (class "Default")
      (node (ref "C11") (pin "2") (pinfunction "2_2") (pintype "passive"))
      (node (ref "U4") (pin "5") (pinfunction "OSC_IN/PD0_5") (pintype "input"))
      (node (ref "X1") (pin "3") (pinfunction "3_3") (pintype "passive"))
    )
    (net (code "73") (name "Net-(U4-OSC_OUT{slash}PD1)") (class "Default")
      (node (ref "C13") (pin "2") (pinfunction "2_2") (pintype "passive"))
      (node (ref "U4") (pin "6") (pinfunction "OSC_OUT/PD1_6") (pintype "output"))
      (node (ref "X1") (pin "1") (pinfunction "1_1") (pintype "passive"))
    )
    (net (code "74") (name "Net-(U4-PB2{slash}BOOT1)") (class "Default")
      (node (ref "R29") (pin "1") (pinfunction "1_1") (pintype "passive"))
      (node (ref "U4") (pin "20") (pinfunction "PB2/BOOT1_20") (pintype "bidirectional"))
    )
    (net (code "75") (name "Net-(U4-PC14-OSC32_IN)") (class "Default")
      (node (ref "C12") (pin "1") (pinfunction "1_1") (pintype "passive"))
      (node (ref "U4") (pin "3") (pinfunction "PC14-OSC32_IN_3") (pintype "bidirectional"))
      (node (ref "X2") (pin "2") (pinfunction "2_2") (pintype "passive"))
    )
    (net (code "76") (name "Net-(U4-PC15-OSC32_OUT)") (class "Default")
      (node (ref "C14") (pin "1") (pinfunction "1_1") (pintype "passive"))
      (node (ref "U4") (pin "4") (pinfunction "PC15-OSC32_OUT_4") (pintype "bidirectional"))
      (node (ref "X2") (pin "1") (pinfunction "1_1") (pintype "passive"))
    )
    (net (code "77") (name "Net-(U4-VBAT)") (class "Default")
      (node (ref "C15") (pin "1") (pinfunction "1_1") (pintype "passive"))
      (node (ref "D10") (pin "2") (pintype "passive"))
      (node (ref "U4") (pin "1") (pinfunction "VBAT_1") (pintype "power_in"))
    )
    (net (code "78") (name "Net-(U4-VDDA)") (class "Default")
      (node (ref "C17") (pin "2") (pinfunction "2_2") (pintype "passive"))
      (node (ref "C18") (pin "2") (pinfunction "2_2") (pintype "passive"))
      (node (ref "R35") (pin "2") (pinfunction "2_2") (pintype "passive"))
      (node (ref "U4") (pin "9") (pinfunction "VDDA_9") (pintype "power_in"))
    )
    (net (code "79") (name "Net-(U5-RXD)") (class "Default")
      (node (ref "R37") (pin "2") (pinfunction "2_2") (pintype "passive"))
      (node (ref "U5") (pin "3") (pinfunction "RXD_3") (pintype "passive"))
    )
    (net (code "80") (name "Net-(U5-TXD)") (class "Default")
      (node (ref "R36") (pin "2") (pinfunction "2_2") (pintype "passive"))
      (node (ref "U5") (pin "2") (pinfunction "TXD_2") (pintype "passive"))
    )
    (net (code "81") (name "Net-(U5-V3)") (class "Default")
      (node (ref "C23") (pin "1") (pinfunction "1_1") (pintype "passive"))
      (node (ref "U5") (pin "4") (pinfunction "V3_4") (pintype "passive"))
    )
    (net (code "82") (name "Net-(U7-IN)") (class "Default")
      (node (ref "JP3") (pin "2") (pinfunction "2_2") (pintype "passive"))
      (node (ref "U7") (pin "3") (pinfunction "IN_3") (pintype "passive"))
    )
    (net (code "83") (name "Net-(V1-+-Pad1)") (class "Default")
      (node (ref "V1") (pin "1") (pinfunction "+_1") (pintype "passive"))
      (node (ref "V1") (pin "4") (pinfunction "-_4") (pintype "passive"))
    )
    (net (code "84") (name "VCC_5V") (class "Default")
      (node (ref "C16") (pin "1") (pinfunction "1_1") (pintype "passive"))
      (node (ref "C19") (pin "1") (pinfunction "1_1") (pintype "passive"))
      (node (ref "C20") (pin "2") (pinfunction "2_2") (pintype "passive"))
      (node (ref "U5") (pin "16") (pinfunction "VCC_16") (pintype "passive"))
      (node (ref "U6") (pin "3") (pinfunction "IN_3") (pintype "passive"))
      (node (ref "U7") (pin "4") (pinfunction "OUT_4") (pintype "passive"))
      (node (ref "USB1") (pin "1") (pinfunction "+5V_1") (pintype "passive"))
    )
    (net (code "85") (name "VCC_BLUE") (class "Default")
      (node (ref "C1") (pin "1") (pinfunction "1_1") (pintype "passive"))
      (node (ref "Q2") (pin "3") (pinfunction "D_3") (pintype "passive"))
      (node (ref "U1") (pin "2") (pinfunction "VCC_2") (pintype "passive"))
    )
    (net (code "86") (name "VCC_NB") (class "Default")
      (node (ref "C2") (pin "1") (pinfunction "1_1") (pintype "passive"))
      (node (ref "C3") (pin "2") (pinfunction "2_2") (pintype "passive"))
      (node (ref "Q4") (pin "3") (pinfunction "D_3") (pintype "passive"))
      (node (ref "U2") (pin "39") (pinfunction "VBAT_39") (pintype "passive"))
      (node (ref "U2") (pin "40") (pinfunction "VBAT_40") (pintype "passive"))
    )
    (net (code "87") (name "unconnected-(U1-P17-Pad11)") (class "Default")
      (node (ref "U1") (pin "11") (pinfunction "P17_11") (pintype "passive"))
    )
    (net (code "88") (name "unconnected-(U1-P27-Pad3)") (class "Default")
      (node (ref "U1") (pin "3") (pinfunction "P27_3") (pintype "passive"))
    )
    (net (code "89") (name "unconnected-(U1-P28{slash}AIN4-Pad4)") (class "Default")
      (node (ref "U1") (pin "4") (pinfunction "P28/AIN4_4") (pintype "passive"))
    )
    (net (code "90") (name "unconnected-(U1-P29{slash}AIN5-Pad5)") (class "Default")
      (node (ref "U1") (pin "5") (pinfunction "P29/AIN5_5") (pintype "passive"))
    )
    (net (code "91") (name "unconnected-(U1-P30{slash}AIN6-Pad6)") (class "Default")
      (node (ref "U1") (pin "6") (pinfunction "P30/AIN6_6") (pintype "passive"))
    )
    (net (code "92") (name "unconnected-(U1-P31{slash}AIN7-Pad7)") (class "Default")
      (node (ref "U1") (pin "7") (pinfunction "P31/AIN7_7") (pintype "passive"))
    )
    (net (code "93") (name "unconnected-(U1-SWCLK-Pad15)") (class "Default")
      (node (ref "U1") (pin "15") (pinfunction "SWCLK_15") (pintype "passive"))
    )
    (net (code "94") (name "unconnected-(U1-SWDIO-Pad16)") (class "Default")
      (node (ref "U1") (pin "16") (pinfunction "SWDIO_16") (pintype "passive"))
    )
    (net (code "95") (name "unconnected-(U2-ADC-Pad33)") (class "Default")
      (node (ref "U2") (pin "33") (pinfunction "ADC_33") (pintype "passive"))
    )
    (net (code "96") (name "unconnected-(U2-AIO<0>-Pad32)") (class "Default")
      (node (ref "U2") (pin "32") (pinfunction "AIO<0>_32") (pintype "passive"))
    )
    (net (code "97") (name "unconnected-(U2-DBG_RXD-Pad25)") (class "Default")
      (node (ref "U2") (pin "25") (pinfunction "DBG_RXD_25") (pintype "passive"))
    )
    (net (code "98") (name "unconnected-(U2-DBG_TXD-Pad26)") (class "Default")
      (node (ref "U2") (pin "26") (pinfunction "DBG_TXD_26") (pintype "passive"))
    )
    (net (code "99") (name "unconnected-(U2-GPIO11-Pad6)") (class "Default")
      (node (ref "U2") (pin "6") (pinfunction "GPIO11_6") (pintype "passive"))
    )
    (net (code "100") (name "unconnected-(U2-NC-Pad3)") (class "Default")
      (node (ref "U2") (pin "3") (pinfunction "NC_3") (pintype "passive"))
    )
    (net (code "101") (name "unconnected-(U2-NC-Pad4)") (class "Default")
      (node (ref "U2") (pin "4") (pinfunction "NC_4") (pintype "passive"))
    )
    (net (code "102") (name "unconnected-(U2-NC-Pad5)") (class "Default")
      (node (ref "U2") (pin "5") (pinfunction "NC_5") (pintype "passive"))
    )
    (net (code "103") (name "unconnected-(U2-NC-Pad8)") (class "Default")
      (node (ref "U2") (pin "8") (pinfunction "NC_8") (pintype "passive"))
    )
    (net (code "104") (name "unconnected-(U2-NC-Pad10)") (class "Default")
      (node (ref "U2") (pin "10") (pinfunction "NC_10") (pintype "passive"))
    )
    (net (code "105") (name "unconnected-(U2-NC-Pad11)") (class "Default")
      (node (ref "U2") (pin "11") (pinfunction "NC_11") (pintype "passive"))
    )
    (net (code "106") (name "unconnected-(U2-NC-Pad12)") (class "Default")
      (node (ref "U2") (pin "12") (pinfunction "NC_12") (pintype "passive"))
    )
    (net (code "107") (name "unconnected-(U2-RI-Pad34)") (class "Default")
      (node (ref "U2") (pin "34") (pinfunction "RI_34") (pintype "passive"))
    )
    (net (code "108") (name "unconnected-(U2-RIO<1>-Pad9)") (class "Default")
      (node (ref "U2") (pin "9") (pinfunction "RIO<1>_9") (pintype "passive"))
    )
    (net (code "109") (name "unconnected-(U2-SWD_DIO-Pad36)") (class "Default")
      (node (ref "U2") (pin "36") (pinfunction "SWD_DIO_36") (pintype "passive"))
    )
    (net (code "110") (name "unconnected-(U2-VDD_EXT-Pad7)") (class "Default")
      (node (ref "U2") (pin "7") (pinfunction "VDD_EXT_7") (pintype "passive"))
    )
    (net (code "111") (name "unconnected-(U3-VPP-Pad5)") (class "Default")
      (node (ref "U3") (pin "5") (pinfunction "VPP_5") (pintype "passive"))
    )
    (net (code "112") (name "unconnected-(U4-PA11-Pad32)") (class "Default")
      (node (ref "U4") (pin "32") (pinfunction "PA11_32") (pintype "bidirectional"))
    )
    (net (code "113") (name "unconnected-(U4-PA15{slash}JTDI-Pad38)") (class "Default")
      (node (ref "U4") (pin "38") (pinfunction "PA15/JTDI_38") (pintype "bidirectional"))
    )
    (net (code "114") (name "unconnected-(U4-PB0-Pad18)") (class "Default")
      (node (ref "U4") (pin "18") (pinfunction "PB0_18") (pintype "bidirectional"))
    )
    (net (code "115") (name "unconnected-(U4-PB1-Pad19)") (class "Default")
      (node (ref "U4") (pin "19") (pinfunction "PB1_19") (pintype "bidirectional"))
    )
    (net (code "116") (name "unconnected-(U4-PB15-Pad28)") (class "Default")
      (node (ref "U4") (pin "28") (pinfunction "PB15_28") (pintype "bidirectional"))
    )
    (net (code "117") (name "unconnected-(U4-PC13-TAMPER-RTC-Pad2)") (class "Default")
      (node (ref "U4") (pin "2") (pinfunction "PC13-TAMPER-RTC_2") (pintype "bidirectional"))
    )
    (net (code "118") (name "unconnected-(U5-CTS-Pad9)") (class "Default")
      (node (ref "U5") (pin "9") (pinfunction "CTS_9") (pintype "passive"))
    )
    (net (code "119") (name "unconnected-(U5-DSR-Pad10)") (class "Default")
      (node (ref "U5") (pin "10") (pinfunction "DSR_10") (pintype "passive"))
    )
    (net (code "120") (name "unconnected-(U5-DTR-Pad13)") (class "Default")
      (node (ref "U5") (pin "13") (pinfunction "DTR_13") (pintype "passive"))
    )
    (net (code "121") (name "unconnected-(U5-R233-Pad15)") (class "Default")
      (node (ref "U5") (pin "15") (pinfunction "R233_15") (pintype "passive"))
    )
    (net (code "122") (name "unconnected-(U5-RCD-Pad12)") (class "Default")
      (node (ref "U5") (pin "12") (pinfunction "RCD_12") (pintype "passive"))
    )
    (net (code "123") (name "unconnected-(U5-RI-Pad11)") (class "Default")
      (node (ref "U5") (pin "11") (pinfunction "RI_11") (pintype "passive"))
    )
    (net (code "124") (name "unconnected-(U5-RTS-Pad14)") (class "Default")
      (node (ref "U5") (pin "14") (pinfunction "RTS_14") (pintype "passive"))
    )
    (net (code "125") (name "unconnected-(U5-XD-Pad8)") (class "Default")
      (node (ref "U5") (pin "8") (pinfunction "XD_8") (pintype "passive"))
    )
    (net (code "126") (name "unconnected-(U5-XI-Pad7)") (class "Default")
      (node (ref "U5") (pin "7") (pinfunction "XI_7") (pintype "passive"))
    )
    (net (code "127") (name "unconnected-(U7-OUT-Pad2)") (class "Default")
      (node (ref "U7") (pin "2") (pinfunction "OUT_2") (pintype "passive"))
    )
    (net (code "128") (name "unconnected-(X1-Pad2)") (class "Default")
      (node (ref "X1") (pin "2") (pinfunction "2_2") (pintype "passive"))
    )
    (net (code "129") (name "unconnected-(X1-Pad4)") (class "Default")
      (node (ref "X1") (pin "4") (pinfunction "4_4") (pintype "passive"))
    )
  )
)
